# LED_Controller.net
KiCad netlist of a schematic drawn in EAGLE
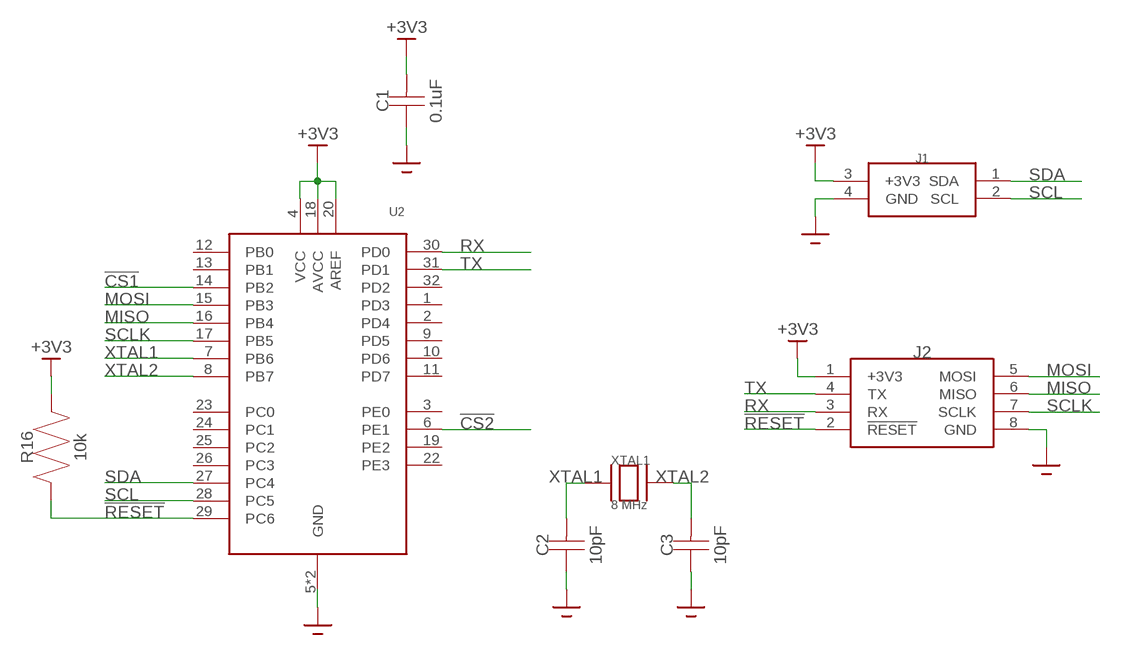
[diagram p0: schematic, sheet 1]
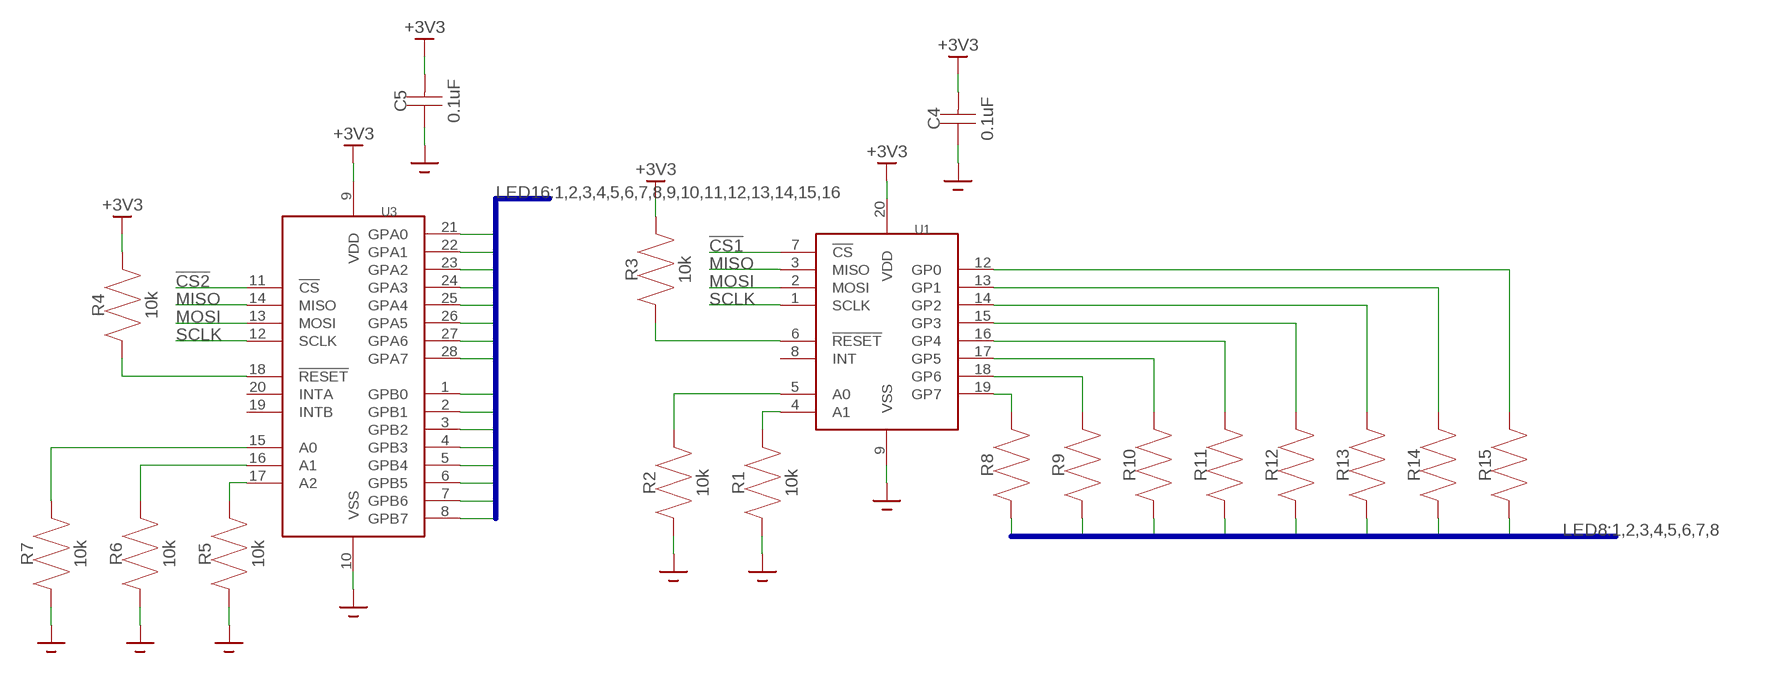
[diagram p1: schematic, sheet 2]
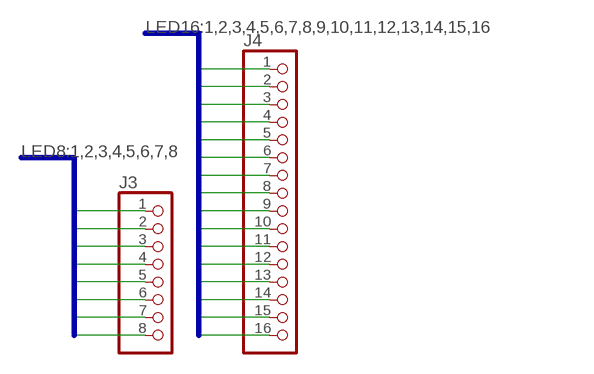
[diagram p2: schematic, sheet 3]

(export (version "E")
  (design (tool "Eeschema 10.0.6"))
  (components
    (comp (ref "C4")
      (value "0.1uF")
      (footprint "eagle-import:0805")
      (libsource (lib "eagle-import") (part "CAPACITOR0805"))
    )
    (comp (ref "C5")
      (value "0.1uF")
      (footprint "eagle-import:0805")
      (libsource (lib "eagle-import") (part "CAPACITOR0805"))
    )
    (comp (ref "R1")
      (value "10k")
      (footprint "eagle-import:0805")
      (libsource (lib "eagle-import") (part "RESISTOR0805"))
    )
    (comp (ref "R2")
      (value "10k")
      (footprint "eagle-import:0805")
      (libsource (lib "eagle-import") (part "RESISTOR0805"))
    )
    (comp (ref "R3")
      (value "10k")
      (footprint "eagle-import:0805")
      (libsource (lib "eagle-import") (part "RESISTOR0805"))
    )
    (comp (ref "R4")
      (value "10k")
      (footprint "eagle-import:0805")
      (libsource (lib "eagle-import") (part "RESISTOR0805"))
    )
    (comp (ref "R5")
      (value "10k")
      (footprint "eagle-import:0805")
      (libsource (lib "eagle-import") (part "RESISTOR0805"))
    )
    (comp (ref "R6")
      (value "10k")
      (footprint "eagle-import:0805")
      (libsource (lib "eagle-import") (part "RESISTOR0805"))
    )
    (comp (ref "R7")
      (value "10k")
      (footprint "eagle-import:0805")
      (libsource (lib "eagle-import") (part "RESISTOR0805"))
    )
    (comp (ref "R8")
      (value "RESISTOR0805")
      (footprint "eagle-import:0805")
      (libsource (lib "eagle-import") (part "RESISTOR0805"))
    )
    (comp (ref "R9")
      (value "RESISTOR0805")
      (footprint "eagle-import:0805")
      (libsource (lib "eagle-import") (part "RESISTOR0805"))
    )
    (comp (ref "R10")
      (value "RESISTOR0805")
      (footprint "eagle-import:0805")
      (libsource (lib "eagle-import") (part "RESISTOR0805"))
    )
    (comp (ref "R11")
      (value "RESISTOR0805")
      (footprint "eagle-import:0805")
      (libsource (lib "eagle-import") (part "RESISTOR0805"))
    )
    (comp (ref "R12")
      (value "RESISTOR0805")
      (footprint "eagle-import:0805")
      (libsource (lib "eagle-import") (part "RESISTOR0805"))
    )
    (comp (ref "R13")
      (value "RESISTOR0805")
      (footprint "eagle-import:0805")
      (libsource (lib "eagle-import") (part "RESISTOR0805"))
    )
    (comp (ref "R14")
      (value "RESISTOR0805")
      (footprint "eagle-import:0805")
      (libsource (lib "eagle-import") (part "RESISTOR0805"))
    )
    (comp (ref "R15")
      (value "RESISTOR0805")
      (footprint "eagle-import:0805")
      (libsource (lib "eagle-import") (part "RESISTOR0805"))
    )
    (comp (ref "U1")
      (value "MCP23S08-E/SO")
      (footprint "eagle-import:MCP23S08-E_SO")
      (libsource (lib "eagle-import") (part "MCP23S08-E/SO"))
    )
    (comp (ref "U3")
      (value "MCP23S17T-E/SO")
      (footprint "eagle-import:MCP23S17T-E_SO")
      (libsource (lib "eagle-import") (part "MCP23S17T-E/SO"))
    )
    (comp (ref "C1")
      (value "0.1uF")
      (footprint "eagle-import:0805")
      (libsource (lib "eagle-import") (part "CAPACITOR0805"))
    )
    (comp (ref "C2")
      (value "10pF")
      (footprint "eagle-import:0805")
      (libsource (lib "eagle-import") (part "CAPACITOR0805"))
    )
    (comp (ref "C3")
      (value "10pF")
      (footprint "eagle-import:0805")
      (libsource (lib "eagle-import") (part "CAPACITOR0805"))
    )
    (comp (ref "J1")
      (value "1-770968-0")
      (footprint "eagle-import:1-770968-0")
      (libsource (lib "eagle-import") (part "1-770968-0"))
    )
    (comp (ref "J2")
      (value "DF1BZ-8DP-2.5DSA")
      (footprint "eagle-import:DF1BZ-8DP-2.5DSA")
      (libsource (lib "eagle-import") (part "DF1BZ-8DP-2.5DSA"))
    )
    (comp (ref "R16")
      (value "10k")
      (footprint "eagle-import:0805")
      (libsource (lib "eagle-import") (part "RESISTOR0805"))
    )
    (comp (ref "U2")
      (value "ATMEGA328PB32-TQFP")
      (footprint "eagle-import:ATMEGA328PB")
      (libsource (lib "eagle-import") (part "ATMEGA328PB32-TQFP"))
    )
    (comp (ref "XTAL1")
      (value "8 MHz")
      (footprint "eagle-import:XRCGB")
      (libsource (lib "eagle-import") (part "XRCGB"))
    )
    (comp (ref "J3")
      (value "LED8")
      (footprint "eagle-import:LED8")
      (libsource (lib "eagle-import") (part "LED8"))
    )
    (comp (ref "J4")
      (value "LED16")
      (footprint "eagle-import:LED16")
      (libsource (lib "eagle-import") (part "LED16"))
    )
  )
  (nets
    (net (code "5") (name "+3V3") (class "Default")
      (node (ref "C1") (pin "P$2") (pinfunction "P$2_P$2") (pintype "passive"))
      (node (ref "C4") (pin "P$2") (pinfunction "P$2_P$2") (pintype "passive"))
      (node (ref "C5") (pin "P$2") (pinfunction "P$2_P$2") (pintype "passive"))
      (node (ref "J1") (pin "3") (pinfunction "+3V3_3") (pintype "power_in"))
      (node (ref "J2") (pin "1") (pinfunction "+3V3_1") (pintype "power_in"))
      (node (ref "R16") (pin "P$2") (pinfunction "P$2_P$2") (pintype "passive"))
      (node (ref "R3") (pin "P$2") (pinfunction "P$2_P$2") (pintype "passive"))
      (node (ref "R4") (pin "P$2") (pinfunction "P$2_P$2") (pintype "passive"))
      (node (ref "U1") (pin "20") (pinfunction "VDD_20") (pintype "bidirectional"))
      (node (ref "U2") (pin "18") (pinfunction "AVCC_18") (pintype "power_in"))
      (node (ref "U2") (pin "20") (pinfunction "AREF_20") (pintype "power_in"))
      (node (ref "U2") (pin "4") (pinfunction "VCC_4") (pintype "power_in"))
      (node (ref "U3") (pin "9") (pinfunction "VDD_9") (pintype "bidirectional"))
    )
    (net (code "10") (name "1") (class "Default")
      (node (ref "J4") (pin "1") (pinfunction "1_1") (pintype "passive"))
      (node (ref "U3") (pin "21") (pinfunction "GPA0_21") (pintype "bidirectional"))
    )
    (net (code "11") (name "2") (class "Default")
      (node (ref "J4") (pin "2") (pinfunction "2_2") (pintype "passive"))
      (node (ref "U3") (pin "22") (pinfunction "GPA1_22") (pintype "bidirectional"))
    )
    (net (code "12") (name "3") (class "Default")
      (node (ref "J4") (pin "3") (pinfunction "3_3") (pintype "passive"))
      (node (ref "U3") (pin "23") (pinfunction "GPA2_23") (pintype "bidirectional"))
    )
    (net (code "13") (name "4") (class "Default")
      (node (ref "J4") (pin "4") (pinfunction "4_4") (pintype "passive"))
      (node (ref "U3") (pin "24") (pinfunction "GPA3_24") (pintype "bidirectional"))
    )
    (net (code "14") (name "5") (class "Default")
      (node (ref "J4") (pin "5") (pinfunction "5_5") (pintype "passive"))
      (node (ref "U3") (pin "25") (pinfunction "GPA4_25") (pintype "bidirectional"))
    )
    (net (code "15") (name "6") (class "Default")
      (node (ref "J4") (pin "6") (pinfunction "6_6") (pintype "passive"))
      (node (ref "U3") (pin "26") (pinfunction "GPA5_26") (pintype "bidirectional"))
    )
    (net (code "16") (name "7") (class "Default")
      (node (ref "J4") (pin "7") (pinfunction "7_7") (pintype "passive"))
      (node (ref "U3") (pin "27") (pinfunction "GPA6_27") (pintype "bidirectional"))
    )
    (net (code "17") (name "8") (class "Default")
      (node (ref "J4") (pin "8") (pinfunction "8_8") (pintype "passive"))
      (node (ref "U3") (pin "28") (pinfunction "GPA7_28") (pintype "bidirectional"))
    )
    (net (code "18") (name "9") (class "Default")
      (node (ref "J4") (pin "9") (pinfunction "9_9") (pintype "passive"))
      (node (ref "U3") (pin "1") (pinfunction "GPB0_1") (pintype "bidirectional"))
    )
    (net (code "19") (name "10") (class "Default")
      (node (ref "J4") (pin "10") (pinfunction "10_10") (pintype "passive"))
      (node (ref "U3") (pin "2") (pinfunction "GPB1_2") (pintype "bidirectional"))
    )
    (net (code "20") (name "11") (class "Default")
      (node (ref "J4") (pin "11") (pinfunction "11_11") (pintype "passive"))
      (node (ref "U3") (pin "3") (pinfunction "GPB2_3") (pintype "bidirectional"))
    )
    (net (code "21") (name "12") (class "Default")
      (node (ref "J4") (pin "12") (pinfunction "12_12") (pintype "passive"))
      (node (ref "U3") (pin "4") (pinfunction "GPB3_4") (pintype "bidirectional"))
    )
    (net (code "22") (name "13") (class "Default")
      (node (ref "J4") (pin "13") (pinfunction "13_13") (pintype "passive"))
      (node (ref "U3") (pin "5") (pinfunction "GPB4_5") (pintype "bidirectional"))
    )
    (net (code "23") (name "14") (class "Default")
      (node (ref "J4") (pin "14") (pinfunction "14_14") (pintype "passive"))
      (node (ref "U3") (pin "6") (pinfunction "GPB5_6") (pintype "bidirectional"))
    )
    (net (code "24") (name "15") (class "Default")
      (node (ref "J4") (pin "15") (pinfunction "15_15") (pintype "passive"))
      (node (ref "U3") (pin "7") (pinfunction "GPB6_7") (pintype "bidirectional"))
    )
    (net (code "25") (name "16") (class "Default")
      (node (ref "J4") (pin "16") (pinfunction "16_16") (pintype "passive"))
      (node (ref "U3") (pin "8") (pinfunction "GPB7_8") (pintype "bidirectional"))
    )
    (net (code "26") (name "A") (class "Default")
      (node (ref "J3") (pin "1") (pinfunction "1_1") (pintype "passive"))
      (node (ref "R15") (pin "P$1") (pinfunction "P$1_P$1") (pintype "passive"))
    )
    (net (code "27") (name "B") (class "Default")
      (node (ref "J3") (pin "2") (pinfunction "2_2") (pintype "passive"))
      (node (ref "R14") (pin "P$1") (pinfunction "P$1_P$1") (pintype "passive"))
    )
    (net (code "28") (name "C") (class "Default")
      (node (ref "J3") (pin "3") (pinfunction "3_3") (pintype "passive"))
      (node (ref "R13") (pin "P$1") (pinfunction "P$1_P$1") (pintype "passive"))
    )
    (net (code "29") (name "D") (class "Default")
      (node (ref "J3") (pin "4") (pinfunction "4_4") (pintype "passive"))
      (node (ref "R12") (pin "P$1") (pinfunction "P$1_P$1") (pintype "passive"))
    )
    (net (code "30") (name "E") (class "Default")
      (node (ref "J3") (pin "5") (pinfunction "5_5") (pintype "passive"))
      (node (ref "R11") (pin "P$1") (pinfunction "P$1_P$1") (pintype "passive"))
    )
    (net (code "31") (name "F") (class "Default")
      (node (ref "J3") (pin "6") (pinfunction "6_6") (pintype "passive"))
      (node (ref "R10") (pin "P$1") (pinfunction "P$1_P$1") (pintype "passive"))
    )
    (net (code "32") (name "G") (class "Default")
      (node (ref "J3") (pin "7") (pinfunction "7_7") (pintype "passive"))
      (node (ref "R9") (pin "P$1") (pinfunction "P$1_P$1") (pintype "passive"))
    )
    (net (code "33") (name "GND") (class "Default")
      (node (ref "C1") (pin "P$1") (pinfunction "P$1_P$1") (pintype "passive"))
      (node (ref "C2") (pin "P$1") (pinfunction "P$1_P$1") (pintype "passive"))
      (node (ref "C3") (pin "P$1") (pinfunction "P$1_P$1") (pintype "passive"))
      (node (ref "C4") (pin "P$1") (pinfunction "P$1_P$1") (pintype "passive"))
      (node (ref "C5") (pin "P$1") (pinfunction "P$1_P$1") (pintype "passive"))
      (node (ref "J1") (pin "4") (pinfunction "GND_4") (pintype "passive"))
      (node (ref "J2") (pin "8") (pinfunction "GND_8") (pintype "passive"))
      (node (ref "R1") (pin "P$1") (pinfunction "P$1_P$1") (pintype "passive"))
      (node (ref "R2") (pin "P$1") (pinfunction "P$1_P$1") (pintype "passive"))
      (node (ref "R5") (pin "P$1") (pinfunction "P$1_P$1") (pintype "passive"))
      (node (ref "R6") (pin "P$1") (pinfunction "P$1_P$1") (pintype "passive"))
      (node (ref "R7") (pin "P$1") (pinfunction "P$1_P$1") (pintype "passive"))
      (node (ref "U1") (pin "9") (pinfunction "VSS_9") (pintype "bidirectional"))
      (node (ref "U2") (pin "21") (pinfunction "GND_21") (pintype "passive"))
      (node (ref "U2") (pin "5") (pinfunction "GND_5") (pintype "passive"))
      (node (ref "U3") (pin "10") (pinfunction "VSS_10") (pintype "bidirectional"))
    )
    (net (code "34") (name "H") (class "Default")
      (node (ref "J3") (pin "8") (pinfunction "8_8") (pintype "passive"))
      (node (ref "R8") (pin "P$1") (pinfunction "P$1_P$1") (pintype "passive"))
    )
    (net (code "35") (name "MISO") (class "Default")
      (node (ref "J2") (pin "6") (pinfunction "MISO_6") (pintype "input"))
      (node (ref "U1") (pin "3") (pinfunction "MISO_3") (pintype "bidirectional"))
      (node (ref "U2") (pin "16") (pinfunction "PB4_16") (pintype "bidirectional"))
      (node (ref "U3") (pin "14") (pinfunction "MISO_14") (pintype "bidirectional"))
    )
    (net (code "36") (name "MOSI") (class "Default")
      (node (ref "J2") (pin "5") (pinfunction "MOSI_5") (pintype "output"))
      (node (ref "U1") (pin "2") (pinfunction "MOSI_2") (pintype "bidirectional"))
      (node (ref "U2") (pin "15") (pinfunction "PB3_15") (pintype "bidirectional"))
      (node (ref "U3") (pin "13") (pinfunction "MOSI_13") (pintype "bidirectional"))
    )
    (net (code "37") (name "Net-(U1-A0)") (class "Default")
      (node (ref "R2") (pin "P$2") (pinfunction "P$2_P$2") (pintype "passive"))
      (node (ref "U1") (pin "5") (pinfunction "A0_5") (pintype "bidirectional"))
    )
    (net (code "38") (name "Net-(U1-A1)") (class "Default")
      (node (ref "R1") (pin "P$2") (pinfunction "P$2_P$2") (pintype "passive"))
      (node (ref "U1") (pin "4") (pinfunction "A1_4") (pintype "bidirectional"))
    )
    (net (code "39") (name "Net-(U1-GP0)") (class "Default")
      (node (ref "R15") (pin "P$2") (pinfunction "P$2_P$2") (pintype "passive"))
      (node (ref "U1") (pin "12") (pinfunction "GP0_12") (pintype "bidirectional"))
    )
    (net (code "40") (name "Net-(U1-GP1)") (class "Default")
      (node (ref "R14") (pin "P$2") (pinfunction "P$2_P$2") (pintype "passive"))
      (node (ref "U1") (pin "13") (pinfunction "GP1_13") (pintype "bidirectional"))
    )
    (net (code "41") (name "Net-(U1-GP2)") (class "Default")
      (node (ref "R13") (pin "P$2") (pinfunction "P$2_P$2") (pintype "passive"))
      (node (ref "U1") (pin "14") (pinfunction "GP2_14") (pintype "bidirectional"))
    )
    (net (code "42") (name "Net-(U1-GP3)") (class "Default")
      (node (ref "R12") (pin "P$2") (pinfunction "P$2_P$2") (pintype "passive"))
      (node (ref "U1") (pin "15") (pinfunction "GP3_15") (pintype "bidirectional"))
    )
    (net (code "43") (name "Net-(U1-GP4)") (class "Default")
      (node (ref "R11") (pin "P$2") (pinfunction "P$2_P$2") (pintype "passive"))
      (node (ref "U1") (pin "16") (pinfunction "GP4_16") (pintype "bidirectional"))
    )
    (net (code "44") (name "Net-(U1-GP5)") (class "Default")
      (node (ref "R10") (pin "P$2") (pinfunction "P$2_P$2") (pintype "passive"))
      (node (ref "U1") (pin "17") (pinfunction "GP5_17") (pintype "bidirectional"))
    )
    (net (code "45") (name "Net-(U1-GP6)") (class "Default")
      (node (ref "R9") (pin "P$2") (pinfunction "P$2_P$2") (pintype "passive"))
      (node (ref "U1") (pin "18") (pinfunction "GP6_18") (pintype "bidirectional"))
    )
    (net (code "46") (name "Net-(U1-GP7)") (class "Default")
      (node (ref "R8") (pin "P$2") (pinfunction "P$2_P$2") (pintype "passive"))
      (node (ref "U1") (pin "19") (pinfunction "GP7_19") (pintype "bidirectional"))
    )
    (net (code "47") (name "Net-(U1-~{RESET})") (class "Default")
      (node (ref "R3") (pin "P$1") (pinfunction "P$1_P$1") (pintype "passive"))
      (node (ref "U1") (pin "6") (pinfunction "~{RESET}_6") (pintype "bidirectional"))
    )
    (net (code "48") (name "Net-(U3-A0)") (class "Default")
      (node (ref "R7") (pin "P$2") (pinfunction "P$2_P$2") (pintype "passive"))
      (node (ref "U3") (pin "15") (pinfunction "A0_15") (pintype "bidirectional"))
    )
    (net (code "49") (name "Net-(U3-A1)") (class "Default")
      (node (ref "R6") (pin "P$2") (pinfunction "P$2_P$2") (pintype "passive"))
      (node (ref "U3") (pin "16") (pinfunction "A1_16") (pintype "bidirectional"))
    )
    (net (code "50") (name "Net-(U3-A2)") (class "Default")
      (node (ref "R5") (pin "P$2") (pinfunction "P$2_P$2") (pintype "passive"))
      (node (ref "U3") (pin "17") (pinfunction "A2_17") (pintype "bidirectional"))
    )
    (net (code "51") (name "Net-(U3-~{RESET})") (class "Default")
      (node (ref "R4") (pin "P$1") (pinfunction "P$1_P$1") (pintype "passive"))
      (node (ref "U3") (pin "18") (pinfunction "~{RESET}_18") (pintype "bidirectional"))
    )
    (net (code "52") (name "RX") (class "Default")
      (node (ref "J2") (pin "3") (pinfunction "RX_3") (pintype "output"))
      (node (ref "U2") (pin "30") (pinfunction "PD0_30") (pintype "bidirectional"))
    )
    (net (code "53") (name "SCL") (class "Default")
      (node (ref "J1") (pin "2") (pinfunction "SCL_2") (pintype "bidirectional"))
      (node (ref "U2") (pin "28") (pinfunction "PC5_28") (pintype "bidirectional"))
    )
    (net (code "54") (name "SCLK") (class "Default")
      (node (ref "J2") (pin "7") (pinfunction "SCLK_7") (pintype "output"))
      (node (ref "U1") (pin "1") (pinfunction "SCLK_1") (pintype "bidirectional"))
      (node (ref "U2") (pin "17") (pinfunction "PB5_17") (pintype "bidirectional"))
      (node (ref "U3") (pin "12") (pinfunction "SCLK_12") (pintype "bidirectional"))
    )
    (net (code "55") (name "SDA") (class "Default")
      (node (ref "J1") (pin "1") (pinfunction "SDA_1") (pintype "bidirectional"))
      (node (ref "U2") (pin "27") (pinfunction "PC4_27") (pintype "bidirectional"))
    )
    (net (code "56") (name "TX") (class "Default")
      (node (ref "J2") (pin "4") (pinfunction "TX_4") (pintype "input"))
      (node (ref "U2") (pin "31") (pinfunction "PD1_31") (pintype "bidirectional"))
    )
    (net (code "57") (name "XTAL1") (class "Default")
      (node (ref "C2") (pin "P$2") (pinfunction "P$2_P$2") (pintype "passive"))
      (node (ref "U2") (pin "7") (pinfunction "PB6_7") (pintype "bidirectional"))
      (node (ref "XTAL1") (pin "1") (pinfunction "P$1_1") (pintype "passive"))
      (node (ref "XTAL1") (pin "3") (pinfunction "P$1_3") (pintype "passive"))
    )
    (net (code "58") (name "XTAL2") (class "Default")
      (node (ref "C3") (pin "P$2") (pinfunction "P$2_P$2") (pintype "passive"))
      (node (ref "U2") (pin "8") (pinfunction "PB7_8") (pintype "bidirectional"))
      (node (ref "XTAL1") (pin "2") (pinfunction "P$2_2") (pintype "passive"))
      (node (ref "XTAL1") (pin "4") (pinfunction "P$2_4") (pintype "passive"))
    )
    (net (code "59") (name "unconnected-(U1-INT-Pad8)") (class "Default")
      (node (ref "U1") (pin "8") (pinfunction "INT_8") (pintype "bidirectional"))
    )
    (net (code "60") (name "unconnected-(U2-PB0-Pad12)") (class "Default")
      (node (ref "U2") (pin "12") (pinfunction "PB0_12") (pintype "bidirectional"))
    )
    (net (code "61") (name "unconnected-(U2-PB1-Pad13)") (class "Default")
      (node (ref "U2") (pin "13") (pinfunction "PB1_13") (pintype "bidirectional"))
    )
    (net (code "62") (name "unconnected-(U2-PC0-Pad23)") (class "Default")
      (node (ref "U2") (pin "23") (pinfunction "PC0_23") (pintype "bidirectional"))
    )
    (net (code "63") (name "unconnected-(U2-PC1-Pad24)") (class "Default")
      (node (ref "U2") (pin "24") (pinfunction "PC1_24") (pintype "bidirectional"))
    )
    (net (code "64") (name "unconnected-(U2-PC2-Pad25)") (class "Default")
      (node (ref "U2") (pin "25") (pinfunction "PC2_25") (pintype "bidirectional"))
    )
    (net (code "65") (name "unconnected-(U2-PC3-Pad26)") (class "Default")
      (node (ref "U2") (pin "26") (pinfunction "PC3_26") (pintype "bidirectional"))
    )
    (net (code "66") (name "unconnected-(U2-PD2-Pad32)") (class "Default")
      (node (ref "U2") (pin "32") (pinfunction "PD2_32") (pintype "bidirectional"))
    )
    (net (code "67") (name "unconnected-(U2-PD3-Pad1)") (class "Default")
      (node (ref "U2") (pin "1") (pinfunction "PD3_1") (pintype "bidirectional"))
    )
    (net (code "68") (name "unconnected-(U2-PD4-Pad2)") (class "Default")
      (node (ref "U2") (pin "2") (pinfunction "PD4_2") (pintype "bidirectional"))
    )
    (net (code "69") (name "unconnected-(U2-PD5-Pad9)") (class "Default")
      (node (ref "U2") (pin "9") (pinfunction "PD5_9") (pintype "bidirectional"))
    )
    (net (code "70") (name "unconnected-(U2-PD6-Pad10)") (class "Default")
      (node (ref "U2") (pin "10") (pinfunction "PD6_10") (pintype "bidirectional"))
    )
    (net (code "71") (name "unconnected-(U2-PD7-Pad11)") (class "Default")
      (node (ref "U2") (pin "11") (pinfunction "PD7_11") (pintype "bidirectional"))
    )
    (net (code "72") (name "unconnected-(U2-PE0-Pad3)") (class "Default")
      (node (ref "U2") (pin "3") (pinfunction "PE0_3") (pintype "bidirectional"))
    )
    (net (code "73") (name "unconnected-(U2-PE2-Pad19)") (class "Default")
      (node (ref "U2") (pin "19") (pinfunction "PE2_19") (pintype "bidirectional"))
    )
    (net (code "74") (name "unconnected-(U2-PE3-Pad22)") (class "Default")
      (node (ref "U2") (pin "22") (pinfunction "PE3_22") (pintype "bidirectional"))
    )
    (net (code "75") (name "unconnected-(U3-INTA-Pad20)") (class "Default")
      (node (ref "U3") (pin "20") (pinfunction "INTA_20") (pintype "bidirectional"))
    )
    (net (code "76") (name "unconnected-(U3-INTB-Pad19)") (class "Default")
      (node (ref "U3") (pin "19") (pinfunction "INTB_19") (pintype "bidirectional"))
    )
    (net (code "77") (name "~{CS1}") (class "Default")
      (node (ref "U1") (pin "7") (pinfunction "~{CS}_7") (pintype "bidirectional"))
      (node (ref "U2") (pin "14") (pinfunction "PB2_14") (pintype "bidirectional"))
    )
    (net (code "78") (name "~{CS2}") (class "Default")
      (node (ref "U2") (pin "6") (pinfunction "PE1_6") (pintype "bidirectional"))
      (node (ref "U3") (pin "11") (pinfunction "~{CS}_11") (pintype "bidirectional"))
    )
    (net (code "79") (name "~{RESET}") (class "Default")
      (node (ref "J2") (pin "2") (pinfunction "~{RESET}_2") (pintype "output"))
      (node (ref "R16") (pin "P$1") (pinfunction "P$1_P$1") (pintype "passive"))
      (node (ref "U2") (pin "29") (pinfunction "PC6_29") (pintype "bidirectional"))
    )
  )
)
